# Signal_Integrity_4L.net
KiCad netlist of a schematic drawn in Altium Designer
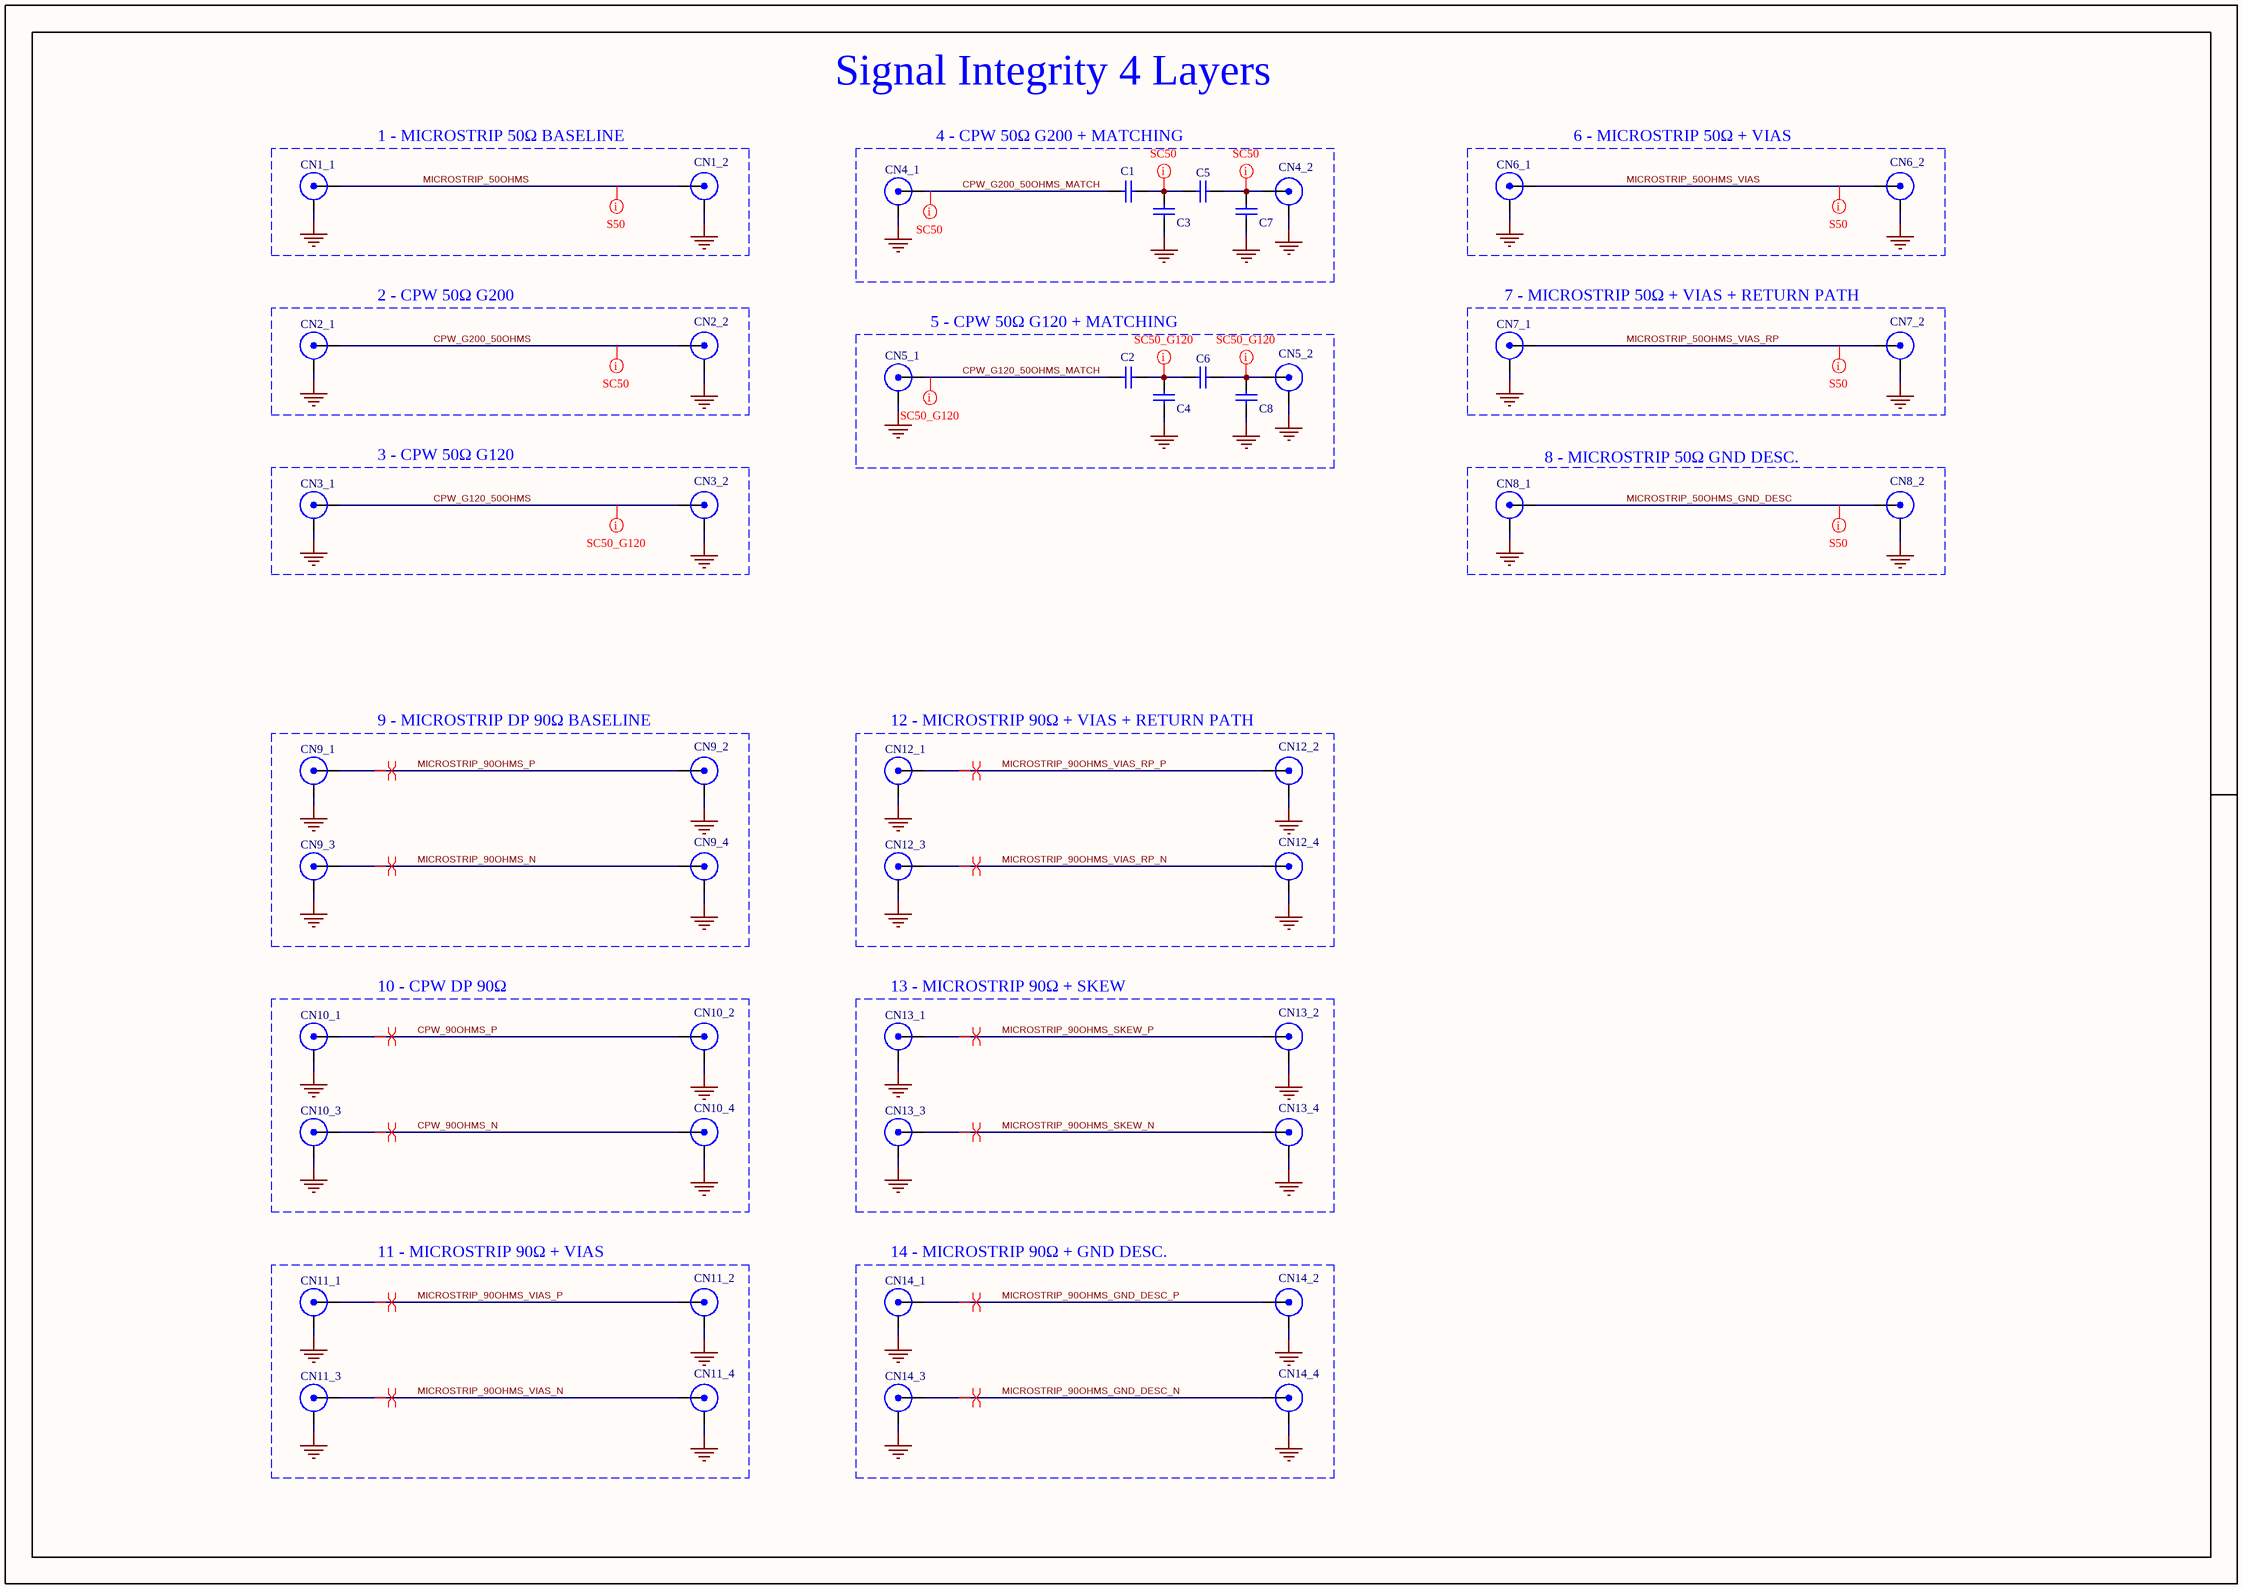
[diagram p0: Signal_Integrity_4L.SchDoc]

(export (version "E")
  (design (tool "Eeschema 10.0.6"))
  (components
    (comp (ref "C1")
      (value "CAP SMD 0402")
      (footprint "0402")
      (description "0402")
      (libsource (lib "Impedance") (part "CAP SMD 0402"))
    )
    (comp (ref "C2")
      (value "CAP SMD 0402")
      (footprint "0402")
      (description "0402")
      (libsource (lib "Impedance") (part "CAP SMD 0402"))
    )
    (comp (ref "C3")
      (value "CAP SMD 0402")
      (footprint "0402")
      (description "0402")
      (libsource (lib "Impedance") (part "CAP SMD 0402"))
    )
    (comp (ref "C4")
      (value "CAP SMD 0402")
      (footprint "0402")
      (description "0402")
      (libsource (lib "Impedance") (part "CAP SMD 0402"))
    )
    (comp (ref "C5")
      (value "CAP SMD 0402")
      (footprint "0402")
      (description "0402")
      (libsource (lib "Impedance") (part "CAP SMD 0402"))
    )
    (comp (ref "C6")
      (value "CAP SMD 0402")
      (footprint "0402")
      (description "0402")
      (libsource (lib "Impedance") (part "CAP SMD 0402"))
    )
    (comp (ref "C7")
      (value "CAP SMD 0402")
      (footprint "0402")
      (description "0402")
      (libsource (lib "Impedance") (part "CAP SMD 0402"))
    )
    (comp (ref "C8")
      (value "CAP SMD 0402")
      (footprint "0402")
      (description "0402")
      (libsource (lib "Impedance") (part "CAP SMD 0402"))
    )
    (comp (ref "CN1_1")
      (value "SMA-KE EDGE")
      (footprint "SMA-KE EDGE")
      (description "SMA Connector Receptacle, Female Socket 50Ohm Board Edge, End Launch Solder")
      (fields
        (field (name "MOUSER PART NUMBER") "712-CONSMA020.062-G")
        (field (name "MANUFACTURER_PART_NUMBER") "CONSMA020.062-G")
      )
      (libsource (lib "Impedance") (part "SMA-KE EDGE"))
    )
    (comp (ref "CN1_2")
      (value "SMA-KE EDGE")
      (footprint "SMA-KE EDGE")
      (description "SMA Connector Receptacle, Female Socket 50Ohm Board Edge, End Launch Solder")
      (fields
        (field (name "MOUSER PART NUMBER") "712-CONSMA020.062-G")
        (field (name "MANUFACTURER_PART_NUMBER") "CONSMA020.062-G")
      )
      (libsource (lib "Impedance") (part "SMA-KE EDGE"))
    )
    (comp (ref "CN2_1")
      (value "SMA-KE EDGE")
      (footprint "SMA-KE EDGE")
      (description "SMA Connector Receptacle, Female Socket 50Ohm Board Edge, End Launch Solder")
      (fields
        (field (name "MOUSER PART NUMBER") "712-CONSMA020.062-G")
        (field (name "MANUFACTURER_PART_NUMBER") "CONSMA020.062-G")
      )
      (libsource (lib "Impedance") (part "SMA-KE EDGE"))
    )
    (comp (ref "CN2_2")
      (value "SMA-KE EDGE")
      (footprint "SMA-KE EDGE")
      (description "SMA Connector Receptacle, Female Socket 50Ohm Board Edge, End Launch Solder")
      (fields
        (field (name "MOUSER PART NUMBER") "712-CONSMA020.062-G")
        (field (name "MANUFACTURER_PART_NUMBER") "CONSMA020.062-G")
      )
      (libsource (lib "Impedance") (part "SMA-KE EDGE"))
    )
    (comp (ref "CN3_1")
      (value "SMA-KE EDGE")
      (footprint "SMA-KE EDGE")
      (description "SMA Connector Receptacle, Female Socket 50Ohm Board Edge, End Launch Solder")
      (fields
        (field (name "MOUSER PART NUMBER") "712-CONSMA020.062-G")
        (field (name "MANUFACTURER_PART_NUMBER") "CONSMA020.062-G")
      )
      (libsource (lib "Impedance") (part "SMA-KE EDGE"))
    )
    (comp (ref "CN3_2")
      (value "SMA-KE EDGE")
      (footprint "SMA-KE EDGE")
      (description "SMA Connector Receptacle, Female Socket 50Ohm Board Edge, End Launch Solder")
      (fields
        (field (name "MOUSER PART NUMBER") "712-CONSMA020.062-G")
        (field (name "MANUFACTURER_PART_NUMBER") "CONSMA020.062-G")
      )
      (libsource (lib "Impedance") (part "SMA-KE EDGE"))
    )
    (comp (ref "CN4_1")
      (value "SMA-KE EDGE")
      (footprint "SMA-KE EDGE")
      (description "SMA Connector Receptacle, Female Socket 50Ohm Board Edge, End Launch Solder")
      (fields
        (field (name "MOUSER PART NUMBER") "712-CONSMA020.062-G")
        (field (name "MANUFACTURER_PART_NUMBER") "CONSMA020.062-G")
      )
      (libsource (lib "Impedance") (part "SMA-KE EDGE"))
    )
    (comp (ref "CN4_2")
      (value "SMA-KE EDGE")
      (footprint "SMA-KE EDGE")
      (description "SMA Connector Receptacle, Female Socket 50Ohm Board Edge, End Launch Solder")
      (fields
        (field (name "MOUSER PART NUMBER") "712-CONSMA020.062-G")
        (field (name "MANUFACTURER_PART_NUMBER") "CONSMA020.062-G")
      )
      (libsource (lib "Impedance") (part "SMA-KE EDGE"))
    )
    (comp (ref "CN5_1")
      (value "SMA-KE EDGE")
      (footprint "SMA-KE EDGE")
      (description "SMA Connector Receptacle, Female Socket 50Ohm Board Edge, End Launch Solder")
      (fields
        (field (name "MOUSER PART NUMBER") "712-CONSMA020.062-G")
        (field (name "MANUFACTURER_PART_NUMBER") "CONSMA020.062-G")
      )
      (libsource (lib "Impedance") (part "SMA-KE EDGE"))
    )
    (comp (ref "CN5_2")
      (value "SMA-KE EDGE")
      (footprint "SMA-KE EDGE")
      (description "SMA Connector Receptacle, Female Socket 50Ohm Board Edge, End Launch Solder")
      (fields
        (field (name "MOUSER PART NUMBER") "712-CONSMA020.062-G")
        (field (name "MANUFACTURER_PART_NUMBER") "CONSMA020.062-G")
      )
      (libsource (lib "Impedance") (part "SMA-KE EDGE"))
    )
    (comp (ref "CN6_1")
      (value "SMA-KE EDGE")
      (footprint "SMA-KE EDGE")
      (description "SMA Connector Receptacle, Female Socket 50Ohm Board Edge, End Launch Solder")
      (fields
        (field (name "MOUSER PART NUMBER") "712-CONSMA020.062-G")
        (field (name "MANUFACTURER_PART_NUMBER") "CONSMA020.062-G")
      )
      (libsource (lib "Impedance") (part "SMA-KE EDGE"))
    )
    (comp (ref "CN6_2")
      (value "SMA-KE EDGE")
      (footprint "SMA-KE EDGE")
      (description "SMA Connector Receptacle, Female Socket 50Ohm Board Edge, End Launch Solder")
      (fields
        (field (name "MOUSER PART NUMBER") "712-CONSMA020.062-G")
        (field (name "MANUFACTURER_PART_NUMBER") "CONSMA020.062-G")
      )
      (libsource (lib "Impedance") (part "SMA-KE EDGE"))
    )
    (comp (ref "CN7_1")
      (value "SMA-KE EDGE")
      (footprint "SMA-KE EDGE")
      (description "SMA Connector Receptacle, Female Socket 50Ohm Board Edge, End Launch Solder")
      (fields
        (field (name "MOUSER PART NUMBER") "712-CONSMA020.062-G")
        (field (name "MANUFACTURER_PART_NUMBER") "CONSMA020.062-G")
      )
      (libsource (lib "Impedance") (part "SMA-KE EDGE"))
    )
    (comp (ref "CN7_2")
      (value "SMA-KE EDGE")
      (footprint "SMA-KE EDGE")
      (description "SMA Connector Receptacle, Female Socket 50Ohm Board Edge, End Launch Solder")
      (fields
        (field (name "MOUSER PART NUMBER") "712-CONSMA020.062-G")
        (field (name "MANUFACTURER_PART_NUMBER") "CONSMA020.062-G")
      )
      (libsource (lib "Impedance") (part "SMA-KE EDGE"))
    )
    (comp (ref "CN8_1")
      (value "SMA-KE EDGE")
      (footprint "SMA-KE EDGE")
      (description "SMA Connector Receptacle, Female Socket 50Ohm Board Edge, End Launch Solder")
      (fields
        (field (name "MOUSER PART NUMBER") "712-CONSMA020.062-G")
        (field (name "MANUFACTURER_PART_NUMBER") "CONSMA020.062-G")
      )
      (libsource (lib "Impedance") (part "SMA-KE EDGE"))
    )
    (comp (ref "CN8_2")
      (value "SMA-KE EDGE")
      (footprint "SMA-KE EDGE")
      (description "SMA Connector Receptacle, Female Socket 50Ohm Board Edge, End Launch Solder")
      (fields
        (field (name "MOUSER PART NUMBER") "712-CONSMA020.062-G")
        (field (name "MANUFACTURER_PART_NUMBER") "CONSMA020.062-G")
      )
      (libsource (lib "Impedance") (part "SMA-KE EDGE"))
    )
    (comp (ref "CN9_1")
      (value "SMA-KE EDGE")
      (footprint "SMA-KE EDGE")
      (description "SMA Connector Receptacle, Female Socket 50Ohm Board Edge, End Launch Solder")
      (fields
        (field (name "MOUSER PART NUMBER") "712-CONSMA020.062-G")
        (field (name "MANUFACTURER_PART_NUMBER") "CONSMA020.062-G")
      )
      (libsource (lib "Impedance") (part "SMA-KE EDGE"))
    )
    (comp (ref "CN9_2")
      (value "SMA-KE EDGE")
      (footprint "SMA-KE EDGE")
      (description "SMA Connector Receptacle, Female Socket 50Ohm Board Edge, End Launch Solder")
      (fields
        (field (name "MOUSER PART NUMBER") "712-CONSMA020.062-G")
        (field (name "MANUFACTURER_PART_NUMBER") "CONSMA020.062-G")
      )
      (libsource (lib "Impedance") (part "SMA-KE EDGE"))
    )
    (comp (ref "CN9_3")
      (value "SMA-KE EDGE")
      (footprint "SMA-KE EDGE")
      (description "SMA Connector Receptacle, Female Socket 50Ohm Board Edge, End Launch Solder")
      (fields
        (field (name "MOUSER PART NUMBER") "712-CONSMA020.062-G")
        (field (name "MANUFACTURER_PART_NUMBER") "CONSMA020.062-G")
      )
      (libsource (lib "Impedance") (part "SMA-KE EDGE"))
    )
    (comp (ref "CN9_4")
      (value "SMA-KE EDGE")
      (footprint "SMA-KE EDGE")
      (description "SMA Connector Receptacle, Female Socket 50Ohm Board Edge, End Launch Solder")
      (fields
        (field (name "MOUSER PART NUMBER") "712-CONSMA020.062-G")
        (field (name "MANUFACTURER_PART_NUMBER") "CONSMA020.062-G")
      )
      (libsource (lib "Impedance") (part "SMA-KE EDGE"))
    )
    (comp (ref "CN10_1")
      (value "SMA-KE EDGE")
      (footprint "SMA-KE EDGE")
      (description "SMA Connector Receptacle, Female Socket 50Ohm Board Edge, End Launch Solder")
      (fields
        (field (name "MOUSER PART NUMBER") "712-CONSMA020.062-G")
        (field (name "MANUFACTURER_PART_NUMBER") "CONSMA020.062-G")
      )
      (libsource (lib "Impedance") (part "SMA-KE EDGE"))
    )
    (comp (ref "CN10_2")
      (value "SMA-KE EDGE")
      (footprint "SMA-KE EDGE")
      (description "SMA Connector Receptacle, Female Socket 50Ohm Board Edge, End Launch Solder")
      (fields
        (field (name "MOUSER PART NUMBER") "712-CONSMA020.062-G")
        (field (name "MANUFACTURER_PART_NUMBER") "CONSMA020.062-G")
      )
      (libsource (lib "Impedance") (part "SMA-KE EDGE"))
    )
    (comp (ref "CN10_3")
      (value "SMA-KE EDGE")
      (footprint "SMA-KE EDGE")
      (description "SMA Connector Receptacle, Female Socket 50Ohm Board Edge, End Launch Solder")
      (fields
        (field (name "MOUSER PART NUMBER") "712-CONSMA020.062-G")
        (field (name "MANUFACTURER_PART_NUMBER") "CONSMA020.062-G")
      )
      (libsource (lib "Impedance") (part "SMA-KE EDGE"))
    )
    (comp (ref "CN10_4")
      (value "SMA-KE EDGE")
      (footprint "SMA-KE EDGE")
      (description "SMA Connector Receptacle, Female Socket 50Ohm Board Edge, End Launch Solder")
      (fields
        (field (name "MOUSER PART NUMBER") "712-CONSMA020.062-G")
        (field (name "MANUFACTURER_PART_NUMBER") "CONSMA020.062-G")
      )
      (libsource (lib "Impedance") (part "SMA-KE EDGE"))
    )
    (comp (ref "CN11_1")
      (value "SMA-KE EDGE")
      (footprint "SMA-KE EDGE")
      (description "SMA Connector Receptacle, Female Socket 50Ohm Board Edge, End Launch Solder")
      (fields
        (field (name "MOUSER PART NUMBER") "712-CONSMA020.062-G")
        (field (name "MANUFACTURER_PART_NUMBER") "CONSMA020.062-G")
      )
      (libsource (lib "Impedance") (part "SMA-KE EDGE"))
    )
    (comp (ref "CN11_2")
      (value "SMA-KE EDGE")
      (footprint "SMA-KE EDGE")
      (description "SMA Connector Receptacle, Female Socket 50Ohm Board Edge, End Launch Solder")
      (fields
        (field (name "MOUSER PART NUMBER") "712-CONSMA020.062-G")
        (field (name "MANUFACTURER_PART_NUMBER") "CONSMA020.062-G")
      )
      (libsource (lib "Impedance") (part "SMA-KE EDGE"))
    )
    (comp (ref "CN11_3")
      (value "SMA-KE EDGE")
      (footprint "SMA-KE EDGE")
      (description "SMA Connector Receptacle, Female Socket 50Ohm Board Edge, End Launch Solder")
      (fields
        (field (name "MOUSER PART NUMBER") "712-CONSMA020.062-G")
        (field (name "MANUFACTURER_PART_NUMBER") "CONSMA020.062-G")
      )
      (libsource (lib "Impedance") (part "SMA-KE EDGE"))
    )
    (comp (ref "CN11_4")
      (value "SMA-KE EDGE")
      (footprint "SMA-KE EDGE")
      (description "SMA Connector Receptacle, Female Socket 50Ohm Board Edge, End Launch Solder")
      (fields
        (field (name "MOUSER PART NUMBER") "712-CONSMA020.062-G")
        (field (name "MANUFACTURER_PART_NUMBER") "CONSMA020.062-G")
      )
      (libsource (lib "Impedance") (part "SMA-KE EDGE"))
    )
    (comp (ref "CN12_1")
      (value "SMA-KE EDGE")
      (footprint "SMA-KE EDGE")
      (description "SMA Connector Receptacle, Female Socket 50Ohm Board Edge, End Launch Solder")
      (fields
        (field (name "MOUSER PART NUMBER") "712-CONSMA020.062-G")
        (field (name "MANUFACTURER_PART_NUMBER") "CONSMA020.062-G")
      )
      (libsource (lib "Impedance") (part "SMA-KE EDGE"))
    )
    (comp (ref "CN12_2")
      (value "SMA-KE EDGE")
      (footprint "SMA-KE EDGE")
      (description "SMA Connector Receptacle, Female Socket 50Ohm Board Edge, End Launch Solder")
      (fields
        (field (name "MOUSER PART NUMBER") "712-CONSMA020.062-G")
        (field (name "MANUFACTURER_PART_NUMBER") "CONSMA020.062-G")
      )
      (libsource (lib "Impedance") (part "SMA-KE EDGE"))
    )
    (comp (ref "CN12_3")
      (value "SMA-KE EDGE")
      (footprint "SMA-KE EDGE")
      (description "SMA Connector Receptacle, Female Socket 50Ohm Board Edge, End Launch Solder")
      (fields
        (field (name "MOUSER PART NUMBER") "712-CONSMA020.062-G")
        (field (name "MANUFACTURER_PART_NUMBER") "CONSMA020.062-G")
      )
      (libsource (lib "Impedance") (part "SMA-KE EDGE"))
    )
    (comp (ref "CN12_4")
      (value "SMA-KE EDGE")
      (footprint "SMA-KE EDGE")
      (description "SMA Connector Receptacle, Female Socket 50Ohm Board Edge, End Launch Solder")
      (fields
        (field (name "MOUSER PART NUMBER") "712-CONSMA020.062-G")
        (field (name "MANUFACTURER_PART_NUMBER") "CONSMA020.062-G")
      )
      (libsource (lib "Impedance") (part "SMA-KE EDGE"))
    )
    (comp (ref "CN13_1")
      (value "SMA-KE EDGE")
      (footprint "SMA-KE EDGE")
      (description "SMA Connector Receptacle, Female Socket 50Ohm Board Edge, End Launch Solder")
      (fields
        (field (name "MOUSER PART NUMBER") "712-CONSMA020.062-G")
        (field (name "MANUFACTURER_PART_NUMBER") "CONSMA020.062-G")
      )
      (libsource (lib "Impedance") (part "SMA-KE EDGE"))
    )
    (comp (ref "CN13_2")
      (value "SMA-KE EDGE")
      (footprint "SMA-KE EDGE")
      (description "SMA Connector Receptacle, Female Socket 50Ohm Board Edge, End Launch Solder")
      (fields
        (field (name "MOUSER PART NUMBER") "712-CONSMA020.062-G")
        (field (name "MANUFACTURER_PART_NUMBER") "CONSMA020.062-G")
      )
      (libsource (lib "Impedance") (part "SMA-KE EDGE"))
    )
    (comp (ref "CN13_3")
      (value "SMA-KE EDGE")
      (footprint "SMA-KE EDGE")
      (description "SMA Connector Receptacle, Female Socket 50Ohm Board Edge, End Launch Solder")
      (fields
        (field (name "MOUSER PART NUMBER") "712-CONSMA020.062-G")
        (field (name "MANUFACTURER_PART_NUMBER") "CONSMA020.062-G")
      )
      (libsource (lib "Impedance") (part "SMA-KE EDGE"))
    )
    (comp (ref "CN13_4")
      (value "SMA-KE EDGE")
      (footprint "SMA-KE EDGE")
      (description "SMA Connector Receptacle, Female Socket 50Ohm Board Edge, End Launch Solder")
      (fields
        (field (name "MOUSER PART NUMBER") "712-CONSMA020.062-G")
        (field (name "MANUFACTURER_PART_NUMBER") "CONSMA020.062-G")
      )
      (libsource (lib "Impedance") (part "SMA-KE EDGE"))
    )
    (comp (ref "CN14_1")
      (value "SMA-KE EDGE")
      (footprint "SMA-KE EDGE")
      (description "SMA Connector Receptacle, Female Socket 50Ohm Board Edge, End Launch Solder")
      (fields
        (field (name "MOUSER PART NUMBER") "712-CONSMA020.062-G")
        (field (name "MANUFACTURER_PART_NUMBER") "CONSMA020.062-G")
      )
      (libsource (lib "Impedance") (part "SMA-KE EDGE"))
    )
    (comp (ref "CN14_2")
      (value "SMA-KE EDGE")
      (footprint "SMA-KE EDGE")
      (description "SMA Connector Receptacle, Female Socket 50Ohm Board Edge, End Launch Solder")
      (fields
        (field (name "MOUSER PART NUMBER") "712-CONSMA020.062-G")
        (field (name "MANUFACTURER_PART_NUMBER") "CONSMA020.062-G")
      )
      (libsource (lib "Impedance") (part "SMA-KE EDGE"))
    )
    (comp (ref "CN14_3")
      (value "SMA-KE EDGE")
      (footprint "SMA-KE EDGE")
      (description "SMA Connector Receptacle, Female Socket 50Ohm Board Edge, End Launch Solder")
      (fields
        (field (name "MOUSER PART NUMBER") "712-CONSMA020.062-G")
        (field (name "MANUFACTURER_PART_NUMBER") "CONSMA020.062-G")
      )
      (libsource (lib "Impedance") (part "SMA-KE EDGE"))
    )
    (comp (ref "CN14_4")
      (value "SMA-KE EDGE")
      (footprint "SMA-KE EDGE")
      (description "SMA Connector Receptacle, Female Socket 50Ohm Board Edge, End Launch Solder")
      (fields
        (field (name "MOUSER PART NUMBER") "712-CONSMA020.062-G")
        (field (name "MANUFACTURER_PART_NUMBER") "CONSMA020.062-G")
      )
      (libsource (lib "Impedance") (part "SMA-KE EDGE"))
    )
  )
  (nets
    (net (code "1") (name "/CPW_90OHMS_N") (class "Default")
      (node (ref "CN10_3") (pin "1") (pinfunction "SIGNAL_1") (pintype "passive"))
      (node (ref "CN10_4") (pin "1") (pinfunction "SIGNAL_1") (pintype "passive"))
    )
    (net (code "2") (name "/CPW_90OHMS_P") (class "Default")
      (node (ref "CN10_1") (pin "1") (pinfunction "SIGNAL_1") (pintype "passive"))
      (node (ref "CN10_2") (pin "1") (pinfunction "SIGNAL_1") (pintype "passive"))
    )
    (net (code "3") (name "/CPW_G120_50OHMS") (class "Default")
      (node (ref "CN3_1") (pin "1") (pinfunction "SIGNAL_1") (pintype "passive"))
      (node (ref "CN3_2") (pin "1") (pinfunction "SIGNAL_1") (pintype "passive"))
    )
    (net (code "4") (name "/CPW_G120_50OHMS_MATCH") (class "Default")
      (node (ref "C2") (pin "1") (pinfunction "1_1") (pintype "passive"))
      (node (ref "CN5_1") (pin "1") (pinfunction "SIGNAL_1") (pintype "passive"))
    )
    (net (code "5") (name "/CPW_G200_50OHMS") (class "Default")
      (node (ref "CN2_1") (pin "1") (pinfunction "SIGNAL_1") (pintype "passive"))
      (node (ref "CN2_2") (pin "1") (pinfunction "SIGNAL_1") (pintype "passive"))
    )
    (net (code "6") (name "/CPW_G200_50OHMS_MATCH") (class "Default")
      (node (ref "C1") (pin "1") (pinfunction "1_1") (pintype "passive"))
      (node (ref "CN4_1") (pin "1") (pinfunction "SIGNAL_1") (pintype "passive"))
    )
    (net (code "7") (name "/MICROSTRIP_50OHMS") (class "Default")
      (node (ref "CN1_1") (pin "1") (pinfunction "SIGNAL_1") (pintype "passive"))
      (node (ref "CN1_2") (pin "1") (pinfunction "SIGNAL_1") (pintype "passive"))
    )
    (net (code "8") (name "/MICROSTRIP_50OHMS_GND_DESC") (class "Default")
      (node (ref "CN8_1") (pin "1") (pinfunction "SIGNAL_1") (pintype "passive"))
      (node (ref "CN8_2") (pin "1") (pinfunction "SIGNAL_1") (pintype "passive"))
    )
    (net (code "9") (name "/MICROSTRIP_50OHMS_VIAS") (class "Default")
      (node (ref "CN6_1") (pin "1") (pinfunction "SIGNAL_1") (pintype "passive"))
      (node (ref "CN6_2") (pin "1") (pinfunction "SIGNAL_1") (pintype "passive"))
    )
    (net (code "10") (name "/MICROSTRIP_50OHMS_VIAS_RP") (class "Default")
      (node (ref "CN7_1") (pin "1") (pinfunction "SIGNAL_1") (pintype "passive"))
      (node (ref "CN7_2") (pin "1") (pinfunction "SIGNAL_1") (pintype "passive"))
    )
    (net (code "11") (name "/MICROSTRIP_90OHMS_GND_DESC_N") (class "Default")
      (node (ref "CN14_3") (pin "1") (pinfunction "SIGNAL_1") (pintype "passive"))
      (node (ref "CN14_4") (pin "1") (pinfunction "SIGNAL_1") (pintype "passive"))
    )
    (net (code "12") (name "/MICROSTRIP_90OHMS_GND_DESC_P") (class "Default")
      (node (ref "CN14_1") (pin "1") (pinfunction "SIGNAL_1") (pintype "passive"))
      (node (ref "CN14_2") (pin "1") (pinfunction "SIGNAL_1") (pintype "passive"))
    )
    (net (code "13") (name "/MICROSTRIP_90OHMS_N") (class "Default")
      (node (ref "CN9_3") (pin "1") (pinfunction "SIGNAL_1") (pintype "passive"))
      (node (ref "CN9_4") (pin "1") (pinfunction "SIGNAL_1") (pintype "passive"))
    )
    (net (code "14") (name "/MICROSTRIP_90OHMS_P") (class "Default")
      (node (ref "CN9_1") (pin "1") (pinfunction "SIGNAL_1") (pintype "passive"))
      (node (ref "CN9_2") (pin "1") (pinfunction "SIGNAL_1") (pintype "passive"))
    )
    (net (code "15") (name "/MICROSTRIP_90OHMS_SKEW_N") (class "Default")
      (node (ref "CN13_3") (pin "1") (pinfunction "SIGNAL_1") (pintype "passive"))
      (node (ref "CN13_4") (pin "1") (pinfunction "SIGNAL_1") (pintype "passive"))
    )
    (net (code "16") (name "/MICROSTRIP_90OHMS_SKEW_P") (class "Default")
      (node (ref "CN13_1") (pin "1") (pinfunction "SIGNAL_1") (pintype "passive"))
      (node (ref "CN13_2") (pin "1") (pinfunction "SIGNAL_1") (pintype "passive"))
    )
    (net (code "17") (name "/MICROSTRIP_90OHMS_VIAS_N") (class "Default")
      (node (ref "CN11_3") (pin "1") (pinfunction "SIGNAL_1") (pintype "passive"))
      (node (ref "CN11_4") (pin "1") (pinfunction "SIGNAL_1") (pintype "passive"))
    )
    (net (code "18") (name "/MICROSTRIP_90OHMS_VIAS_P") (class "Default")
      (node (ref "CN11_1") (pin "1") (pinfunction "SIGNAL_1") (pintype "passive"))
      (node (ref "CN11_2") (pin "1") (pinfunction "SIGNAL_1") (pintype "passive"))
    )
    (net (code "19") (name "/MICROSTRIP_90OHMS_VIAS_RP_N") (class "Default")
      (node (ref "CN12_3") (pin "1") (pinfunction "SIGNAL_1") (pintype "passive"))
      (node (ref "CN12_4") (pin "1") (pinfunction "SIGNAL_1") (pintype "passive"))
    )
    (net (code "20") (name "/MICROSTRIP_90OHMS_VIAS_RP_P") (class "Default")
      (node (ref "CN12_1") (pin "1") (pinfunction "SIGNAL_1") (pintype "passive"))
      (node (ref "CN12_2") (pin "1") (pinfunction "SIGNAL_1") (pintype "passive"))
    )
    (net (code "21") (name "GND1") (class "Default")
      (node (ref "CN1_1") (pin "2") (pinfunction "GND_2") (pintype "passive"))
      (node (ref "CN1_2") (pin "2") (pinfunction "GND_2") (pintype "passive"))
    )
    (net (code "22") (name "GND2") (class "Default")
      (node (ref "CN2_1") (pin "2") (pinfunction "GND_2") (pintype "passive"))
      (node (ref "CN2_2") (pin "2") (pinfunction "GND_2") (pintype "passive"))
    )
    (net (code "23") (name "GND3") (class "Default")
      (node (ref "CN3_1") (pin "2") (pinfunction "GND_2") (pintype "passive"))
      (node (ref "CN3_2") (pin "2") (pinfunction "GND_2") (pintype "passive"))
    )
    (net (code "24") (name "GND4") (class "Default")
      (node (ref "C3") (pin "1") (pinfunction "1_1") (pintype "passive"))
      (node (ref "C7") (pin "1") (pinfunction "1_1") (pintype "passive"))
      (node (ref "CN4_1") (pin "2") (pinfunction "GND_2") (pintype "passive"))
      (node (ref "CN4_2") (pin "2") (pinfunction "GND_2") (pintype "passive"))
    )
    (net (code "25") (name "GND5") (class "Default")
      (node (ref "C4") (pin "1") (pinfunction "1_1") (pintype "passive"))
      (node (ref "C8") (pin "1") (pinfunction "1_1") (pintype "passive"))
      (node (ref "CN5_1") (pin "2") (pinfunction "GND_2") (pintype "passive"))
      (node (ref "CN5_2") (pin "2") (pinfunction "GND_2") (pintype "passive"))
    )
    (net (code "26") (name "GND6") (class "Default")
      (node (ref "CN6_1") (pin "2") (pinfunction "GND_2") (pintype "passive"))
      (node (ref "CN6_2") (pin "2") (pinfunction "GND_2") (pintype "passive"))
    )
    (net (code "27") (name "GND7") (class "Default")
      (node (ref "CN7_1") (pin "2") (pinfunction "GND_2") (pintype "passive"))
      (node (ref "CN7_2") (pin "2") (pinfunction "GND_2") (pintype "passive"))
    )
    (net (code "28") (name "GND8") (class "Default")
      (node (ref "CN8_1") (pin "2") (pinfunction "GND_2") (pintype "passive"))
      (node (ref "CN8_2") (pin "2") (pinfunction "GND_2") (pintype "passive"))
    )
    (net (code "29") (name "GND9") (class "Default")
      (node (ref "CN9_1") (pin "2") (pinfunction "GND_2") (pintype "passive"))
      (node (ref "CN9_2") (pin "2") (pinfunction "GND_2") (pintype "passive"))
      (node (ref "CN9_3") (pin "2") (pinfunction "GND_2") (pintype "passive"))
      (node (ref "CN9_4") (pin "2") (pinfunction "GND_2") (pintype "passive"))
    )
    (net (code "30") (name "GND10") (class "Default")
      (node (ref "CN10_1") (pin "2") (pinfunction "GND_2") (pintype "passive"))
      (node (ref "CN10_2") (pin "2") (pinfunction "GND_2") (pintype "passive"))
      (node (ref "CN10_3") (pin "2") (pinfunction "GND_2") (pintype "passive"))
      (node (ref "CN10_4") (pin "2") (pinfunction "GND_2") (pintype "passive"))
    )
    (net (code "31") (name "GND11") (class "Default")
      (node (ref "CN11_1") (pin "2") (pinfunction "GND_2") (pintype "passive"))
      (node (ref "CN11_2") (pin "2") (pinfunction "GND_2") (pintype "passive"))
      (node (ref "CN11_3") (pin "2") (pinfunction "GND_2") (pintype "passive"))
      (node (ref "CN11_4") (pin "2") (pinfunction "GND_2") (pintype "passive"))
    )
    (net (code "32") (name "GND12") (class "Default")
      (node (ref "CN12_1") (pin "2") (pinfunction "GND_2") (pintype "passive"))
      (node (ref "CN12_2") (pin "2") (pinfunction "GND_2") (pintype "passive"))
      (node (ref "CN12_3") (pin "2") (pinfunction "GND_2") (pintype "passive"))
      (node (ref "CN12_4") (pin "2") (pinfunction "GND_2") (pintype "passive"))
    )
    (net (code "33") (name "GND13") (class "Default")
      (node (ref "CN13_1") (pin "2") (pinfunction "GND_2") (pintype "passive"))
      (node (ref "CN13_2") (pin "2") (pinfunction "GND_2") (pintype "passive"))
      (node (ref "CN13_3") (pin "2") (pinfunction "GND_2") (pintype "passive"))
      (node (ref "CN13_4") (pin "2") (pinfunction "GND_2") (pintype "passive"))
    )
    (net (code "34") (name "GND14") (class "Default")
      (node (ref "CN14_1") (pin "2") (pinfunction "GND_2") (pintype "passive"))
      (node (ref "CN14_2") (pin "2") (pinfunction "GND_2") (pintype "passive"))
      (node (ref "CN14_3") (pin "2") (pinfunction "GND_2") (pintype "passive"))
      (node (ref "CN14_4") (pin "2") (pinfunction "GND_2") (pintype "passive"))
    )
    (net (code "35") (name "Net-(C1-Pad2)") (class "Default")
      (node (ref "C1") (pin "2") (pinfunction "2_2") (pintype "passive"))
      (node (ref "C3") (pin "2") (pinfunction "2_2") (pintype "passive"))
      (node (ref "C5") (pin "1") (pinfunction "1_1") (pintype "passive"))
    )
    (net (code "36") (name "Net-(C2-Pad2)") (class "Default")
      (node (ref "C2") (pin "2") (pinfunction "2_2") (pintype "passive"))
      (node (ref "C4") (pin "2") (pinfunction "2_2") (pintype "passive"))
      (node (ref "C6") (pin "1") (pinfunction "1_1") (pintype "passive"))
    )
    (net (code "37") (name "Net-(CN4_2-SIGNAL)") (class "Default")
      (node (ref "C5") (pin "2") (pinfunction "2_2") (pintype "passive"))
      (node (ref "C7") (pin "2") (pinfunction "2_2") (pintype "passive"))
      (node (ref "CN4_2") (pin "1") (pinfunction "SIGNAL_1") (pintype "passive"))
    )
    (net (code "38") (name "Net-(CN5_2-SIGNAL)") (class "Default")
      (node (ref "C6") (pin "2") (pinfunction "2_2") (pintype "passive"))
      (node (ref "C8") (pin "2") (pinfunction "2_2") (pintype "passive"))
      (node (ref "CN5_2") (pin "1") (pinfunction "SIGNAL_1") (pintype "passive"))
    )
  )
)
